# Greinke_Boost_Converter.net
KiCad netlist of a schematic drawn in Altium Designer
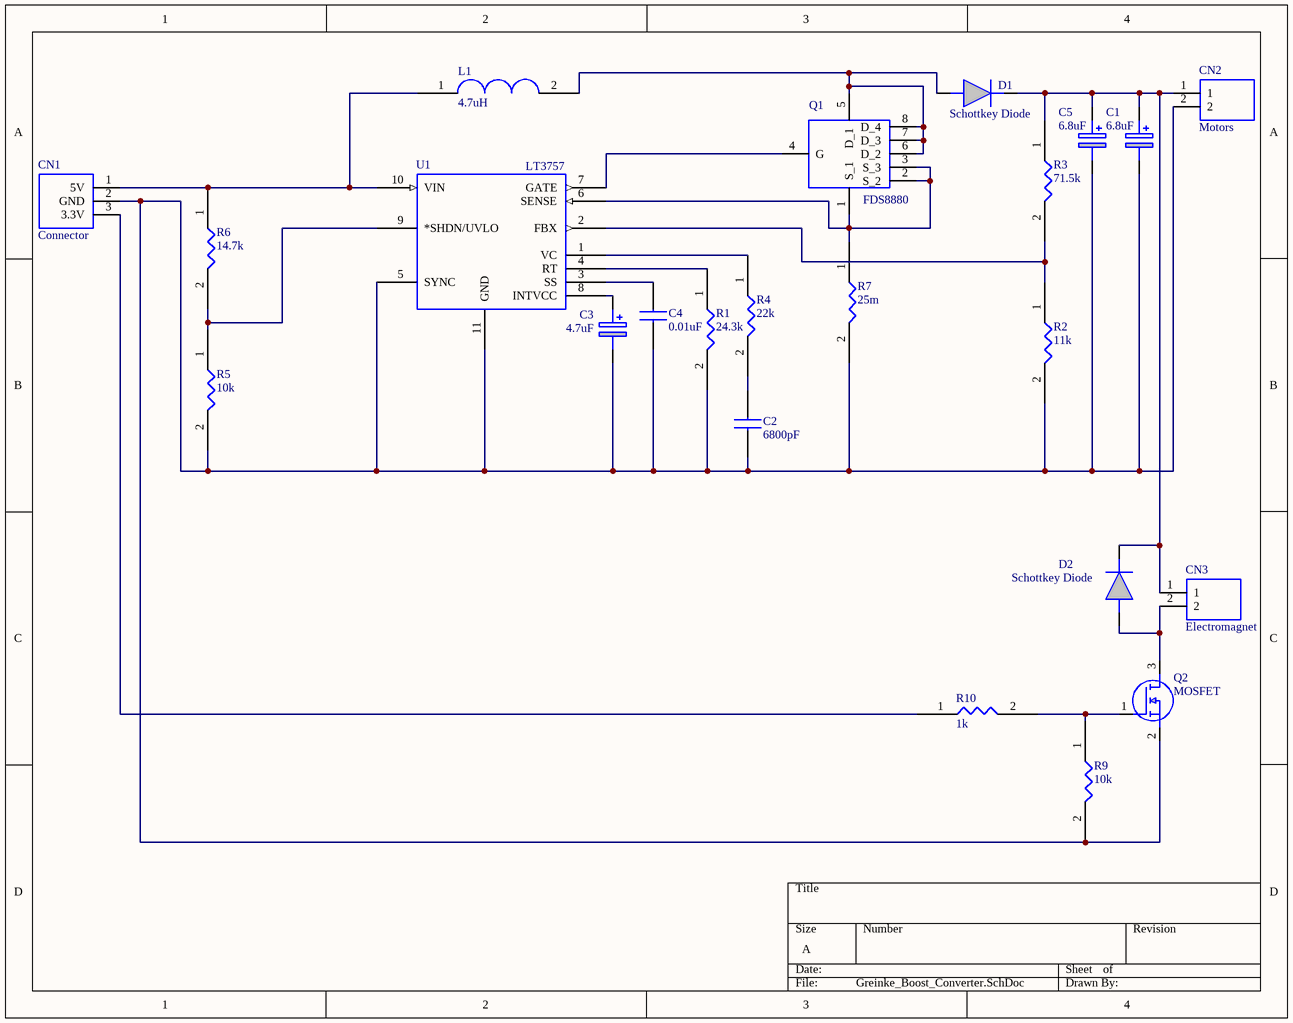
[diagram p0: Greinke_Boost_Converter.SchDoc]

(export (version "E")
  (design (tool "Eeschema 10.0.6"))
  (components
    (comp (ref "C1")
      (value "6.8uF")
      (footprint "6.8u Capacitor")
      (libsource (lib "Schlib1") (part "6.8u Capacitor"))
    )
    (comp (ref "C2")
      (value "6800pF")
      (footprint "6800p Capacitor")
      (libsource (lib "Schlib1") (part "6800p Capacitor"))
    )
    (comp (ref "C3")
      (value "4.7uF")
      (footprint "4.7u Capacitor")
      (libsource (lib "Schlib1") (part "4.7u Capacitor"))
    )
    (comp (ref "C4")
      (value "0.01uF")
      (footprint "0.01u Capacitor")
      (libsource (lib "Schlib1") (part "0.01u Capacitor_1"))
    )
    (comp (ref "C5")
      (value "6.8uF")
      (footprint "6.8u Capacitor")
      (libsource (lib "Schlib1") (part "6.8u Capacitor"))
    )
    (comp (ref "CN1")
      (value "Connector")
      (footprint "3 Terminal Blocks")
      (libsource (lib "Schlib1") (part "3 Terminal Blocks"))
    )
    (comp (ref "CN2")
      (value "Motors")
      (footprint "2 Terminal Blocks")
      (libsource (lib "Schlib1") (part "2 Terminal Blocks"))
    )
    (comp (ref "CN3")
      (value "Electromagnet")
      (footprint "2 Terminal Blocks")
      (libsource (lib "Schlib1") (part "2 Terminal Blocks"))
    )
    (comp (ref "D1")
      (value "Schottkey Diode")
      (footprint "MBRS340")
      (libsource (lib "Schlib1") (part "MBRS340"))
    )
    (comp (ref "D2")
      (value "Schottkey Diode")
      (footprint "MBRS340")
      (libsource (lib "Schlib1") (part "MBRS340"))
    )
    (comp (ref "L1")
      (value "4.7uH")
      (footprint "4.7uH Inductor")
      (libsource (lib "Schlib1") (part "4.7uH Inductor"))
    )
    (comp (ref "Q1") (value "FDS8880") (footprint "FDS8880") (libsource (lib "Schlib1") (part "FDS8880")))
    (comp (ref "Q2") (value "MOSFET") (footprint "Si2316DS") (libsource (lib "Schlib1") (part "Si2316DS")))
    (comp (ref "R1")
      (value "24.3k")
      (footprint "24.3k Resistor")
      (libsource (lib "Schlib1") (part "24.3k Resistor"))
    )
    (comp (ref "R2")
      (value "11k")
      (footprint "11k Resistor")
      (libsource (lib "Schlib1") (part "11k Resistor"))
    )
    (comp (ref "R3")
      (value "71.5k")
      (footprint "71.5k Resistor")
      (libsource (lib "Schlib1") (part "71.5k Resistor"))
    )
    (comp (ref "R4")
      (value "22k")
      (footprint "22k Resistor")
      (libsource (lib "Schlib1") (part "22k Resistor"))
    )
    (comp (ref "R5")
      (value "10k")
      (footprint "10k Resistor")
      (libsource (lib "Schlib1") (part "10k Resistor"))
    )
    (comp (ref "R6")
      (value "14.7k")
      (footprint "14.7k Resistor")
      (libsource (lib "Schlib1") (part "14.7k Resistor"))
    )
    (comp (ref "R7")
      (value "25m")
      (footprint "25m Resistor")
      (libsource (lib "Schlib1") (part "25m Resistor"))
    )
    (comp (ref "R9")
      (value "10k")
      (footprint "10k Resistor")
      (libsource (lib "Schlib1") (part "10k Resistor"))
    )
    (comp (ref "R10") (value "1k") (footprint "1k Resistor") (libsource (lib "Schlib1") (part "1k Resistor")))
    (comp (ref "U1") (value "LT3757") (footprint "LT3757") (libsource (lib "Schlib1") (part "LT3757")))
  )
  (nets
    (net (code "1") (name "Net-(C1-+)") (class "Default")
      (node (ref "C1") (pin "1") (pinfunction "+_1") (pintype "passive"))
      (node (ref "C5") (pin "1") (pinfunction "+_1") (pintype "passive"))
      (node (ref "CN2") (pin "1") (pinfunction "1_1") (pintype "passive"))
      (node (ref "CN3") (pin "1") (pinfunction "1_1") (pintype "passive"))
      (node (ref "D1") (pin "1") (pinfunction "K_1") (pintype "passive"))
      (node (ref "D2") (pin "1") (pinfunction "K_1") (pintype "passive"))
      (node (ref "R3") (pin "1") (pintype "passive"))
    )
    (net (code "2") (name "Net-(C1--)") (class "Default")
      (node (ref "C1") (pin "2") (pinfunction "-_2") (pintype "passive"))
      (node (ref "C2") (pin "2") (pinfunction "2_2") (pintype "passive"))
      (node (ref "C3") (pin "2") (pinfunction "-_2") (pintype "passive"))
      (node (ref "C4") (pin "1") (pinfunction "1_1") (pintype "passive"))
      (node (ref "C5") (pin "2") (pinfunction "-_2") (pintype "passive"))
      (node (ref "CN1") (pin "2") (pinfunction "GND_2") (pintype "passive"))
      (node (ref "CN2") (pin "2") (pinfunction "2_2") (pintype "passive"))
      (node (ref "Q2") (pin "2") (pinfunction "S_2") (pintype "passive"))
      (node (ref "R1") (pin "2") (pintype "passive"))
      (node (ref "R2") (pin "2") (pintype "passive"))
      (node (ref "R5") (pin "2") (pintype "passive"))
      (node (ref "R7") (pin "2") (pintype "passive"))
      (node (ref "R9") (pin "2") (pintype "passive"))
      (node (ref "U1") (pin "11") (pinfunction "GND_11") (pintype "passive"))
      (node (ref "U1") (pin "5") (pinfunction "SYNC_5") (pintype "passive"))
    )
    (net (code "3") (name "Net-(C2-Pad1)") (class "Default")
      (node (ref "C2") (pin "1") (pinfunction "1_1") (pintype "passive"))
      (node (ref "R4") (pin "2") (pintype "passive"))
    )
    (net (code "4") (name "Net-(C3-+)") (class "Default")
      (node (ref "C3") (pin "1") (pinfunction "+_1") (pintype "passive"))
      (node (ref "U1") (pin "8") (pinfunction "INTVCC_8") (pintype "passive"))
    )
    (net (code "5") (name "Net-(CN1-3.3V)") (class "Default")
      (node (ref "CN1") (pin "3") (pinfunction "3.3V_3") (pintype "passive"))
      (node (ref "R10") (pin "1") (pintype "passive"))
    )
    (net (code "6") (name "Net-(CN1-5V)") (class "Default")
      (node (ref "CN1") (pin "1") (pinfunction "5V_1") (pintype "passive"))
      (node (ref "L1") (pin "1") (pintype "passive"))
      (node (ref "R6") (pin "1") (pintype "passive"))
      (node (ref "U1") (pin "10") (pinfunction "VIN_10") (pintype "input"))
    )
    (net (code "7") (name "Net-(D1-A)") (class "Default")
      (node (ref "D1") (pin "2") (pinfunction "A_2") (pintype "passive"))
      (node (ref "L1") (pin "2") (pintype "passive"))
      (node (ref "Q1") (pin "5") (pinfunction "D_1_5") (pintype "passive"))
      (node (ref "Q1") (pin "6") (pinfunction "D_2_6") (pintype "passive"))
      (node (ref "Q1") (pin "7") (pinfunction "D_3_7") (pintype "passive"))
      (node (ref "Q1") (pin "8") (pinfunction "D_4_8") (pintype "passive"))
    )
    (net (code "8") (name "Net-(D2-A)") (class "Default")
      (node (ref "CN3") (pin "2") (pinfunction "2_2") (pintype "passive"))
      (node (ref "D2") (pin "2") (pinfunction "A_2") (pintype "passive"))
      (node (ref "Q2") (pin "3") (pinfunction "D_3") (pintype "passive"))
    )
    (net (code "9") (name "Net-(Q1-G)") (class "Default")
      (node (ref "Q1") (pin "4") (pinfunction "G_4") (pintype "passive"))
      (node (ref "U1") (pin "7") (pinfunction "GATE_7") (pintype "output"))
    )
    (net (code "10") (name "Net-(Q1-S_1)") (class "Default")
      (node (ref "Q1") (pin "1") (pinfunction "S_1_1") (pintype "passive"))
      (node (ref "Q1") (pin "2") (pinfunction "S_2_2") (pintype "passive"))
      (node (ref "Q1") (pin "3") (pinfunction "S_3_3") (pintype "passive"))
      (node (ref "R7") (pin "1") (pintype "passive"))
      (node (ref "U1") (pin "6") (pinfunction "SENSE_6") (pintype "input"))
    )
    (net (code "11") (name "Net-(Q2-G)") (class "Default")
      (node (ref "Q2") (pin "1") (pinfunction "G_1") (pintype "passive"))
      (node (ref "R10") (pin "2") (pintype "passive"))
      (node (ref "R9") (pin "1") (pintype "passive"))
    )
    (net (code "12") (name "Net-(U1-*SHDN{slash}UVLO)") (class "Default")
      (node (ref "R5") (pin "1") (pintype "passive"))
      (node (ref "R6") (pin "2") (pintype "passive"))
      (node (ref "U1") (pin "9") (pinfunction "*SHDN/UVLO_9") (pintype "passive"))
    )
    (net (code "13") (name "Net-(U1-FBX)") (class "Default")
      (node (ref "R2") (pin "1") (pintype "passive"))
      (node (ref "R3") (pin "2") (pintype "passive"))
      (node (ref "U1") (pin "2") (pinfunction "FBX_2") (pintype "output"))
    )
    (net (code "14") (name "Net-(U1-RT)") (class "Default")
      (node (ref "R1") (pin "1") (pintype "passive"))
      (node (ref "U1") (pin "4") (pinfunction "RT_4") (pintype "passive"))
    )
    (net (code "15") (name "Net-(U1-SS)") (class "Default")
      (node (ref "C4") (pin "2") (pinfunction "2_2") (pintype "passive"))
      (node (ref "U1") (pin "3") (pinfunction "SS_3") (pintype "passive"))
    )
    (net (code "16") (name "Net-(U1-VC)") (class "Default")
      (node (ref "R4") (pin "1") (pintype "passive"))
      (node (ref "U1") (pin "1") (pinfunction "VC_1") (pintype "passive"))
    )
  )
)
